# StepStick-Tester_v10.net
KiCad netlist of a schematic drawn in EAGLE
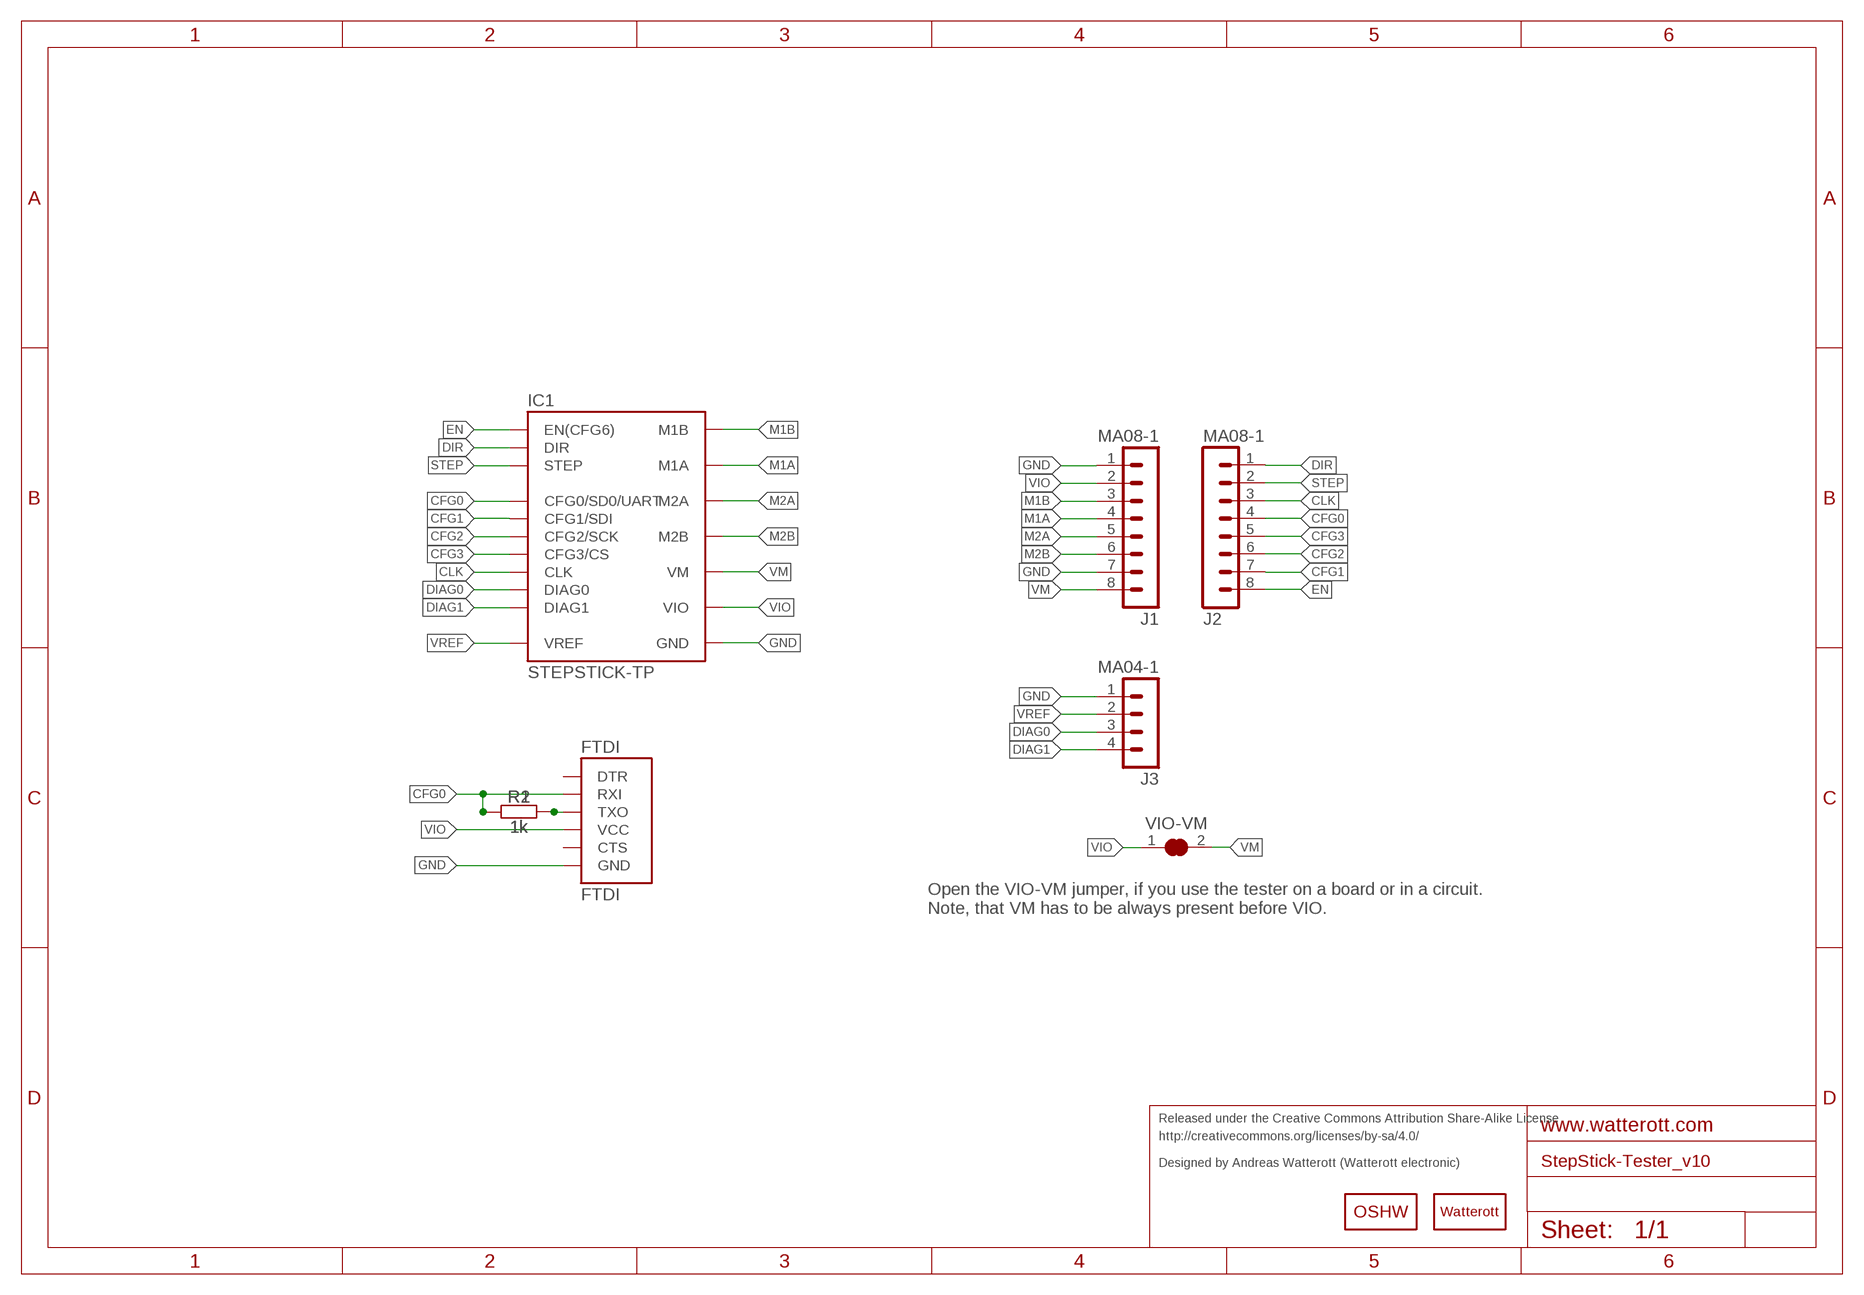
[diagram p0: schematic, sheet 1]

(export (version "E")
  (design (tool "Eeschema 10.0.6"))
  (components
    (comp (ref "FTDI")
      (value "FTDI")
      (footprint "eagle-import:FTDI")
      (libsource (lib "eagle-import") (part "FTDI"))
    )
    (comp (ref "IC1")
      (value "STEPSTICK-TP")
      (footprint "eagle-import:STEPSTICK_TP")
      (libsource (lib "eagle-import") (part "STEPSTICK-TP"))
    )
    (comp (ref "J1")
      (value "MA08-1")
      (footprint "eagle-import:MA08-1")
      (libsource (lib "eagle-import") (part "MA08-1"))
    )
    (comp (ref "J2")
      (value "MA08-1")
      (footprint "eagle-import:MA08-1")
      (libsource (lib "eagle-import") (part "MA08-1"))
    )
    (comp (ref "J3")
      (value "MA04-1")
      (footprint "eagle-import:MA04-1")
      (libsource (lib "eagle-import") (part "MA04-1"))
    )
    (comp (ref "LOGO1")
      (value "OSHW_LOGOX0070")
      (footprint "eagle-import:OSHW_6X70")
      (libsource (lib "eagle-import") (part "OSHW_LOGOX0070"))
    )
    (comp (ref "LOGO2")
      (value "LOGO-S_PLACE_S")
      (footprint "eagle-import:SPARK_TPLACE_S")
      (libsource (lib "eagle-import") (part "LOGO-S_PLACE_S"))
    )
    (comp (ref "R1")
      (value "1k")
      (footprint "eagle-import:R0207_7")
      (libsource (lib "eagle-import") (part "RESISTOR-07"))
    )
    (comp (ref "R2")
      (value "1k")
      (footprint "eagle-import:C0805")
      (libsource (lib "eagle-import") (part "RESISTOR-0805"))
    )
    (comp (ref "VIO-VM")
      (value "JUMPER2-0603-NC")
      (footprint "eagle-import:JUMPER2-0603_NC")
      (libsource (lib "eagle-import") (part "JUMPER2-0603-NC"))
    )
  )
  (nets
    (net (code "1") (name "CFG0") (class "Default")
      (node (ref "FTDI") (pin "5-RXI") (pinfunction "RXI_5-RXI") (pintype "bidirectional"))
      (node (ref "IC1") (pin "NC/CFG0") (pinfunction "CFG0/SD0/UART_NC/CFG0") (pintype "bidirectional"))
      (node (ref "J2") (pin "4") (pinfunction "4_4") (pintype "passive"))
      (node (ref "R1") (pin "1") (pinfunction "1_1") (pintype "passive"))
      (node (ref "R2") (pin "1") (pinfunction "1_1") (pintype "passive"))
    )
    (net (code "2") (name "CFG1") (class "Default")
      (node (ref "IC1") (pin "CFG1") (pinfunction "CFG1/SDI_CFG1") (pintype "bidirectional"))
      (node (ref "J2") (pin "7") (pinfunction "7_7") (pintype "passive"))
    )
    (net (code "3") (name "CFG2") (class "Default")
      (node (ref "IC1") (pin "CFG2") (pinfunction "CFG2/SCK_CFG2") (pintype "bidirectional"))
      (node (ref "J2") (pin "6") (pinfunction "6_6") (pintype "passive"))
    )
    (net (code "4") (name "CFG3") (class "Default")
      (node (ref "IC1") (pin "CFG3") (pinfunction "CFG3/CS_CFG3") (pintype "bidirectional"))
      (node (ref "J2") (pin "5") (pinfunction "5_5") (pintype "passive"))
    )
    (net (code "5") (name "CLK") (class "Default")
      (node (ref "IC1") (pin "NC/CLK") (pinfunction "CLK_NC/CLK") (pintype "bidirectional"))
      (node (ref "J2") (pin "3") (pinfunction "3_3") (pintype "passive"))
    )
    (net (code "6") (name "DIAG0") (class "Default")
      (node (ref "IC1") (pin "DIAG0") (pinfunction "DIAG0_DIAG0") (pintype "bidirectional"))
      (node (ref "J3") (pin "3") (pinfunction "3_3") (pintype "passive"))
    )
    (net (code "7") (name "DIAG1") (class "Default")
      (node (ref "IC1") (pin "DIAG1") (pinfunction "DIAG1_DIAG1") (pintype "bidirectional"))
      (node (ref "J3") (pin "4") (pinfunction "4_4") (pintype "passive"))
    )
    (net (code "8") (name "DIR") (class "Default")
      (node (ref "IC1") (pin "DIR") (pinfunction "DIR_DIR") (pintype "bidirectional"))
      (node (ref "J2") (pin "1") (pinfunction "1_1") (pintype "passive"))
    )
    (net (code "9") (name "EN") (class "Default")
      (node (ref "IC1") (pin "EN") (pinfunction "EN(CFG6)_EN") (pintype "bidirectional"))
      (node (ref "J2") (pin "8") (pinfunction "8_8") (pintype "passive"))
    )
    (net (code "10") (name "GND") (class "Default")
      (node (ref "FTDI") (pin "1-GND") (pinfunction "GND_1-GND") (pintype "power_in"))
      (node (ref "IC1") (pin "GND@1") (pinfunction "GND_GND@1") (pintype "power_in"))
      (node (ref "IC1") (pin "GND@2") (pinfunction "GND_GND@2") (pintype "power_in"))
      (node (ref "J1") (pin "1") (pinfunction "1_1") (pintype "passive"))
      (node (ref "J1") (pin "7") (pinfunction "7_7") (pintype "passive"))
      (node (ref "J3") (pin "1") (pinfunction "1_1") (pintype "passive"))
    )
    (net (code "11") (name "M1A") (class "Default")
      (node (ref "IC1") (pin "M1A") (pinfunction "M1A_M1A") (pintype "output"))
      (node (ref "J1") (pin "4") (pinfunction "4_4") (pintype "passive"))
    )
    (net (code "12") (name "M1B") (class "Default")
      (node (ref "IC1") (pin "M1B") (pinfunction "M1B_M1B") (pintype "output"))
      (node (ref "J1") (pin "3") (pinfunction "3_3") (pintype "passive"))
    )
    (net (code "13") (name "M2A") (class "Default")
      (node (ref "IC1") (pin "M2A") (pinfunction "M2A_M2A") (pintype "output"))
      (node (ref "J1") (pin "5") (pinfunction "5_5") (pintype "passive"))
    )
    (net (code "14") (name "M2B") (class "Default")
      (node (ref "IC1") (pin "M2B") (pinfunction "M2B_M2B") (pintype "output"))
      (node (ref "J1") (pin "6") (pinfunction "6_6") (pintype "passive"))
    )
    (net (code "15") (name "Net-(FTDI-TXO)") (class "Default")
      (node (ref "FTDI") (pin "4-TXO") (pinfunction "TXO_4-TXO") (pintype "bidirectional"))
      (node (ref "R1") (pin "2") (pinfunction "2_2") (pintype "passive"))
      (node (ref "R2") (pin "2") (pinfunction "2_2") (pintype "passive"))
    )
    (net (code "16") (name "STEP") (class "Default")
      (node (ref "IC1") (pin "STEP") (pinfunction "STEP_STEP") (pintype "bidirectional"))
      (node (ref "J2") (pin "2") (pinfunction "2_2") (pintype "passive"))
    )
    (net (code "17") (name "VIO") (class "Default")
      (node (ref "FTDI") (pin "3-VCC") (pinfunction "VCC_3-VCC") (pintype "power_in"))
      (node (ref "IC1") (pin "VIO") (pinfunction "VIO_VIO") (pintype "power_in"))
      (node (ref "J1") (pin "2") (pinfunction "2_2") (pintype "passive"))
      (node (ref "VIO-VM") (pin "1") (pinfunction "1_1") (pintype "passive"))
    )
    (net (code "18") (name "VM") (class "Default")
      (node (ref "IC1") (pin "VM") (pinfunction "VM_VM") (pintype "power_in"))
      (node (ref "J1") (pin "8") (pinfunction "8_8") (pintype "passive"))
      (node (ref "VIO-VM") (pin "2") (pinfunction "2_2") (pintype "passive"))
    )
    (net (code "19") (name "VREF") (class "Default")
      (node (ref "IC1") (pin "VREF") (pinfunction "VREF_VREF") (pintype "passive"))
      (node (ref "J3") (pin "2") (pinfunction "2_2") (pintype "passive"))
    )
    (net (code "20") (name "unconnected-(FTDI-CTS-Pad2-CTS)") (class "Default")
      (node (ref "FTDI") (pin "2-CTS") (pinfunction "CTS_2-CTS") (pintype "bidirectional"))
    )
    (net (code "21") (name "unconnected-(FTDI-DTR-Pad6-DTR)") (class "Default")
      (node (ref "FTDI") (pin "6-DTR") (pinfunction "DTR_6-DTR") (pintype "bidirectional"))
    )
  )
)
